# version4.net
KiCad netlist of a schematic drawn in EAGLE
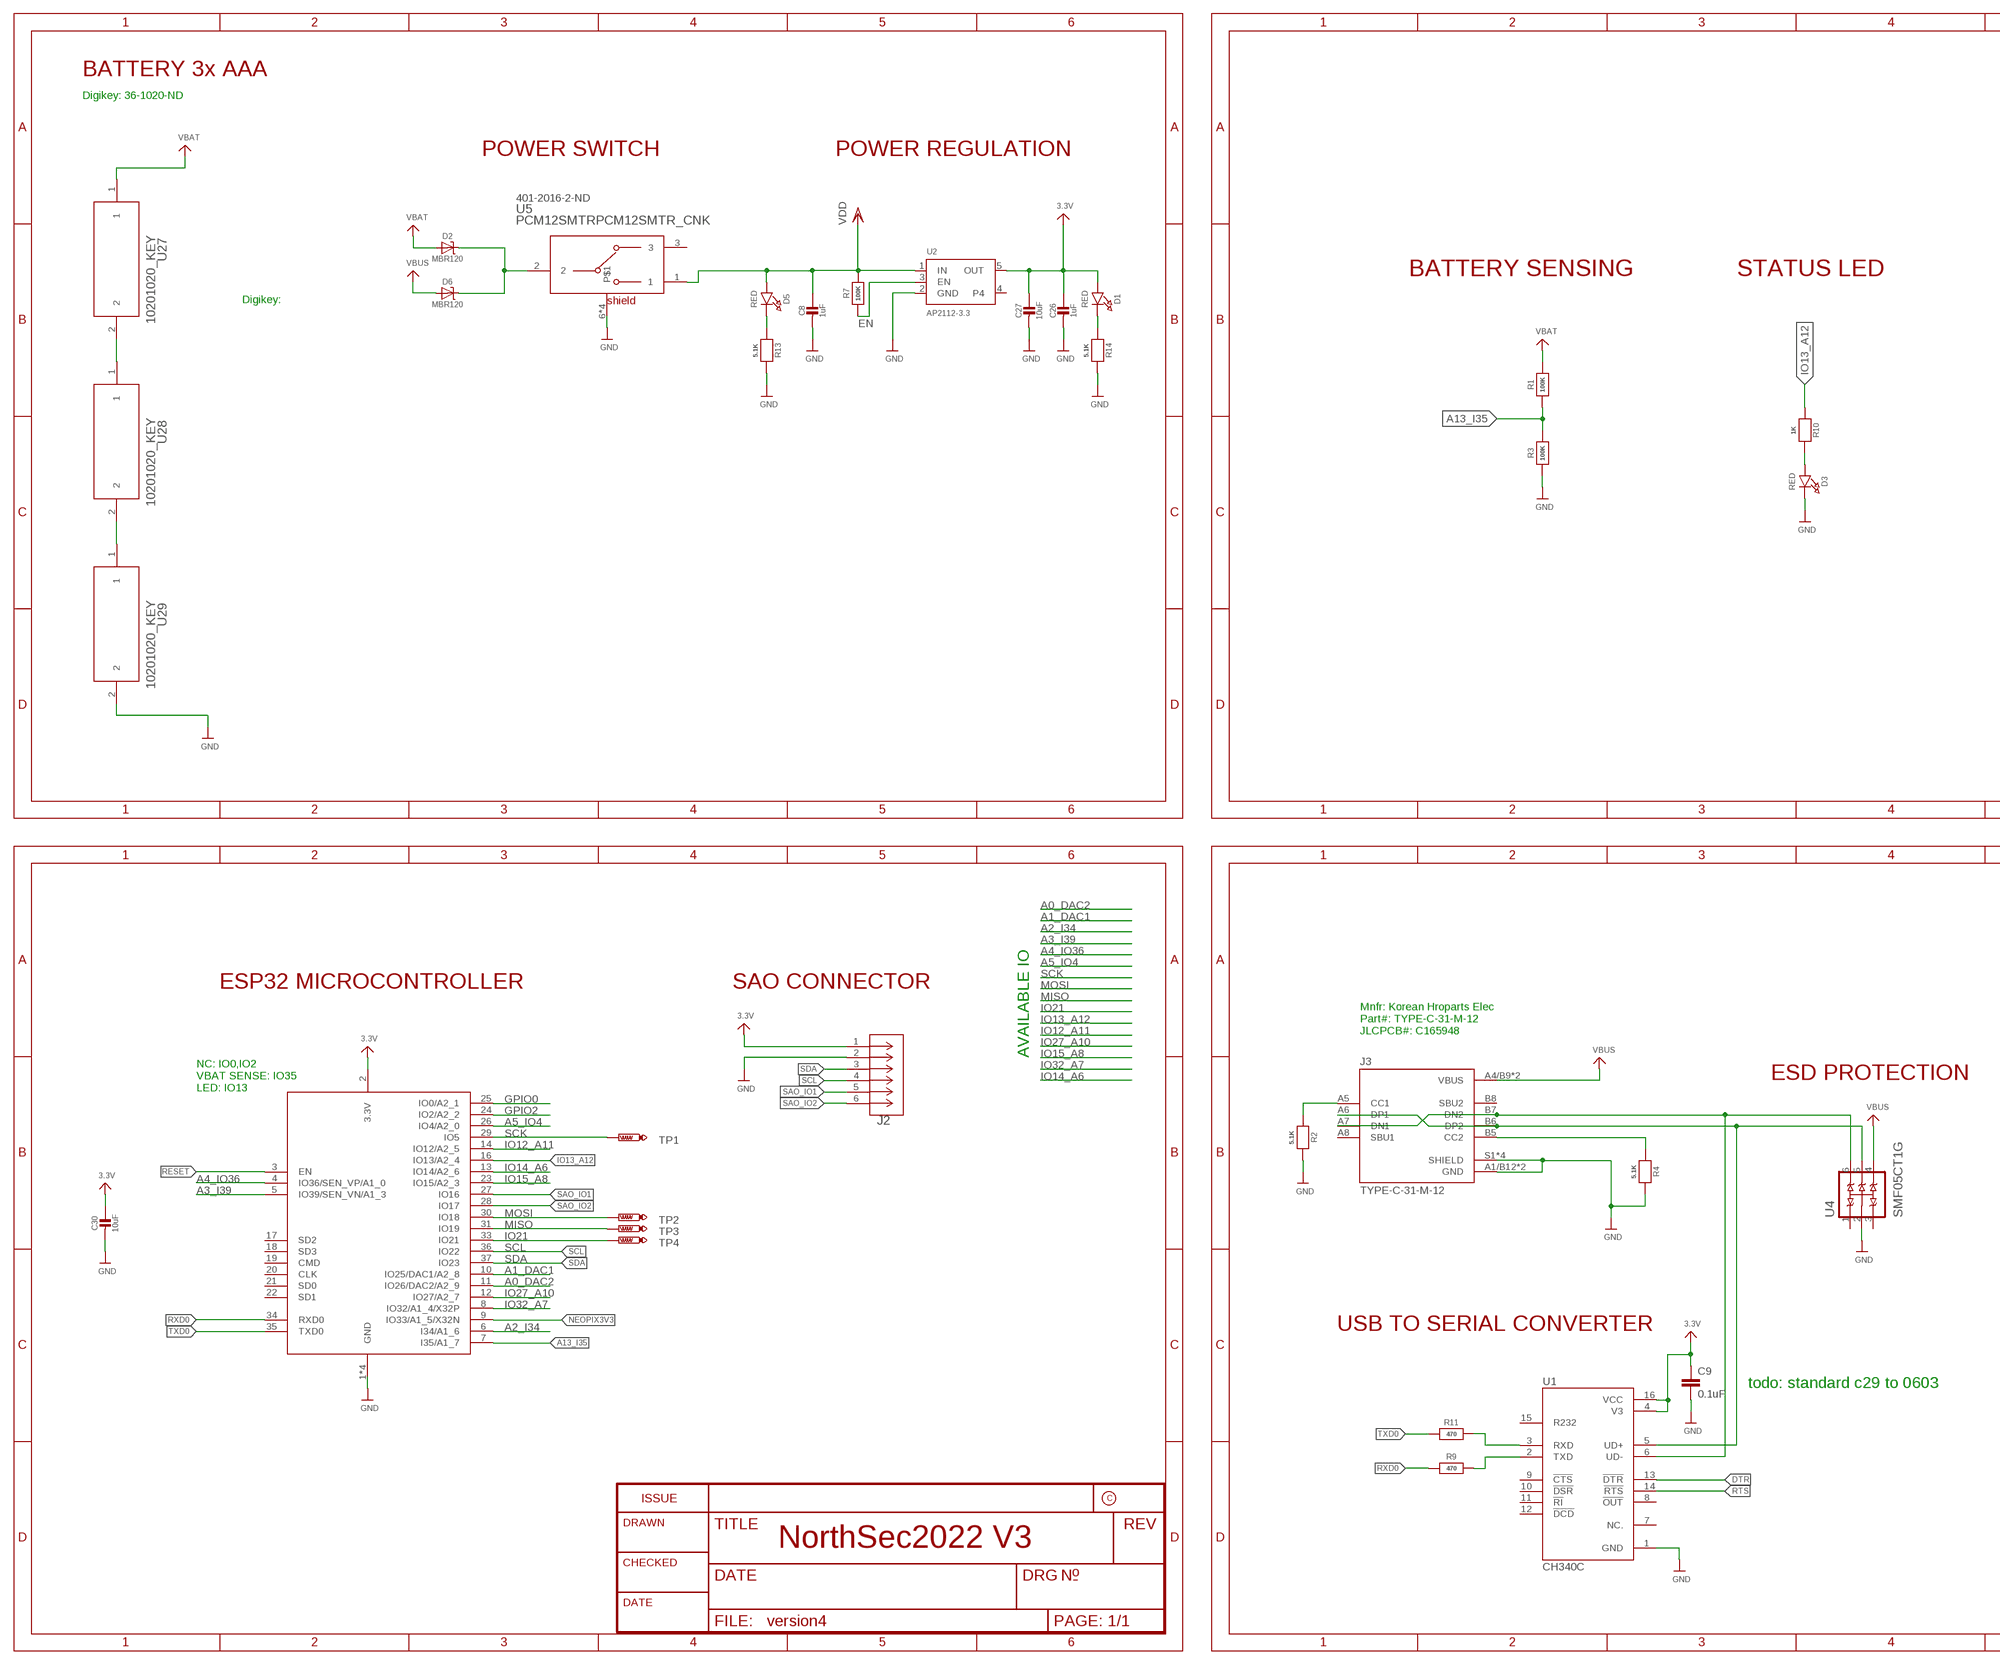
[diagram p0: schematic, sheet 1, part 1 of 2]
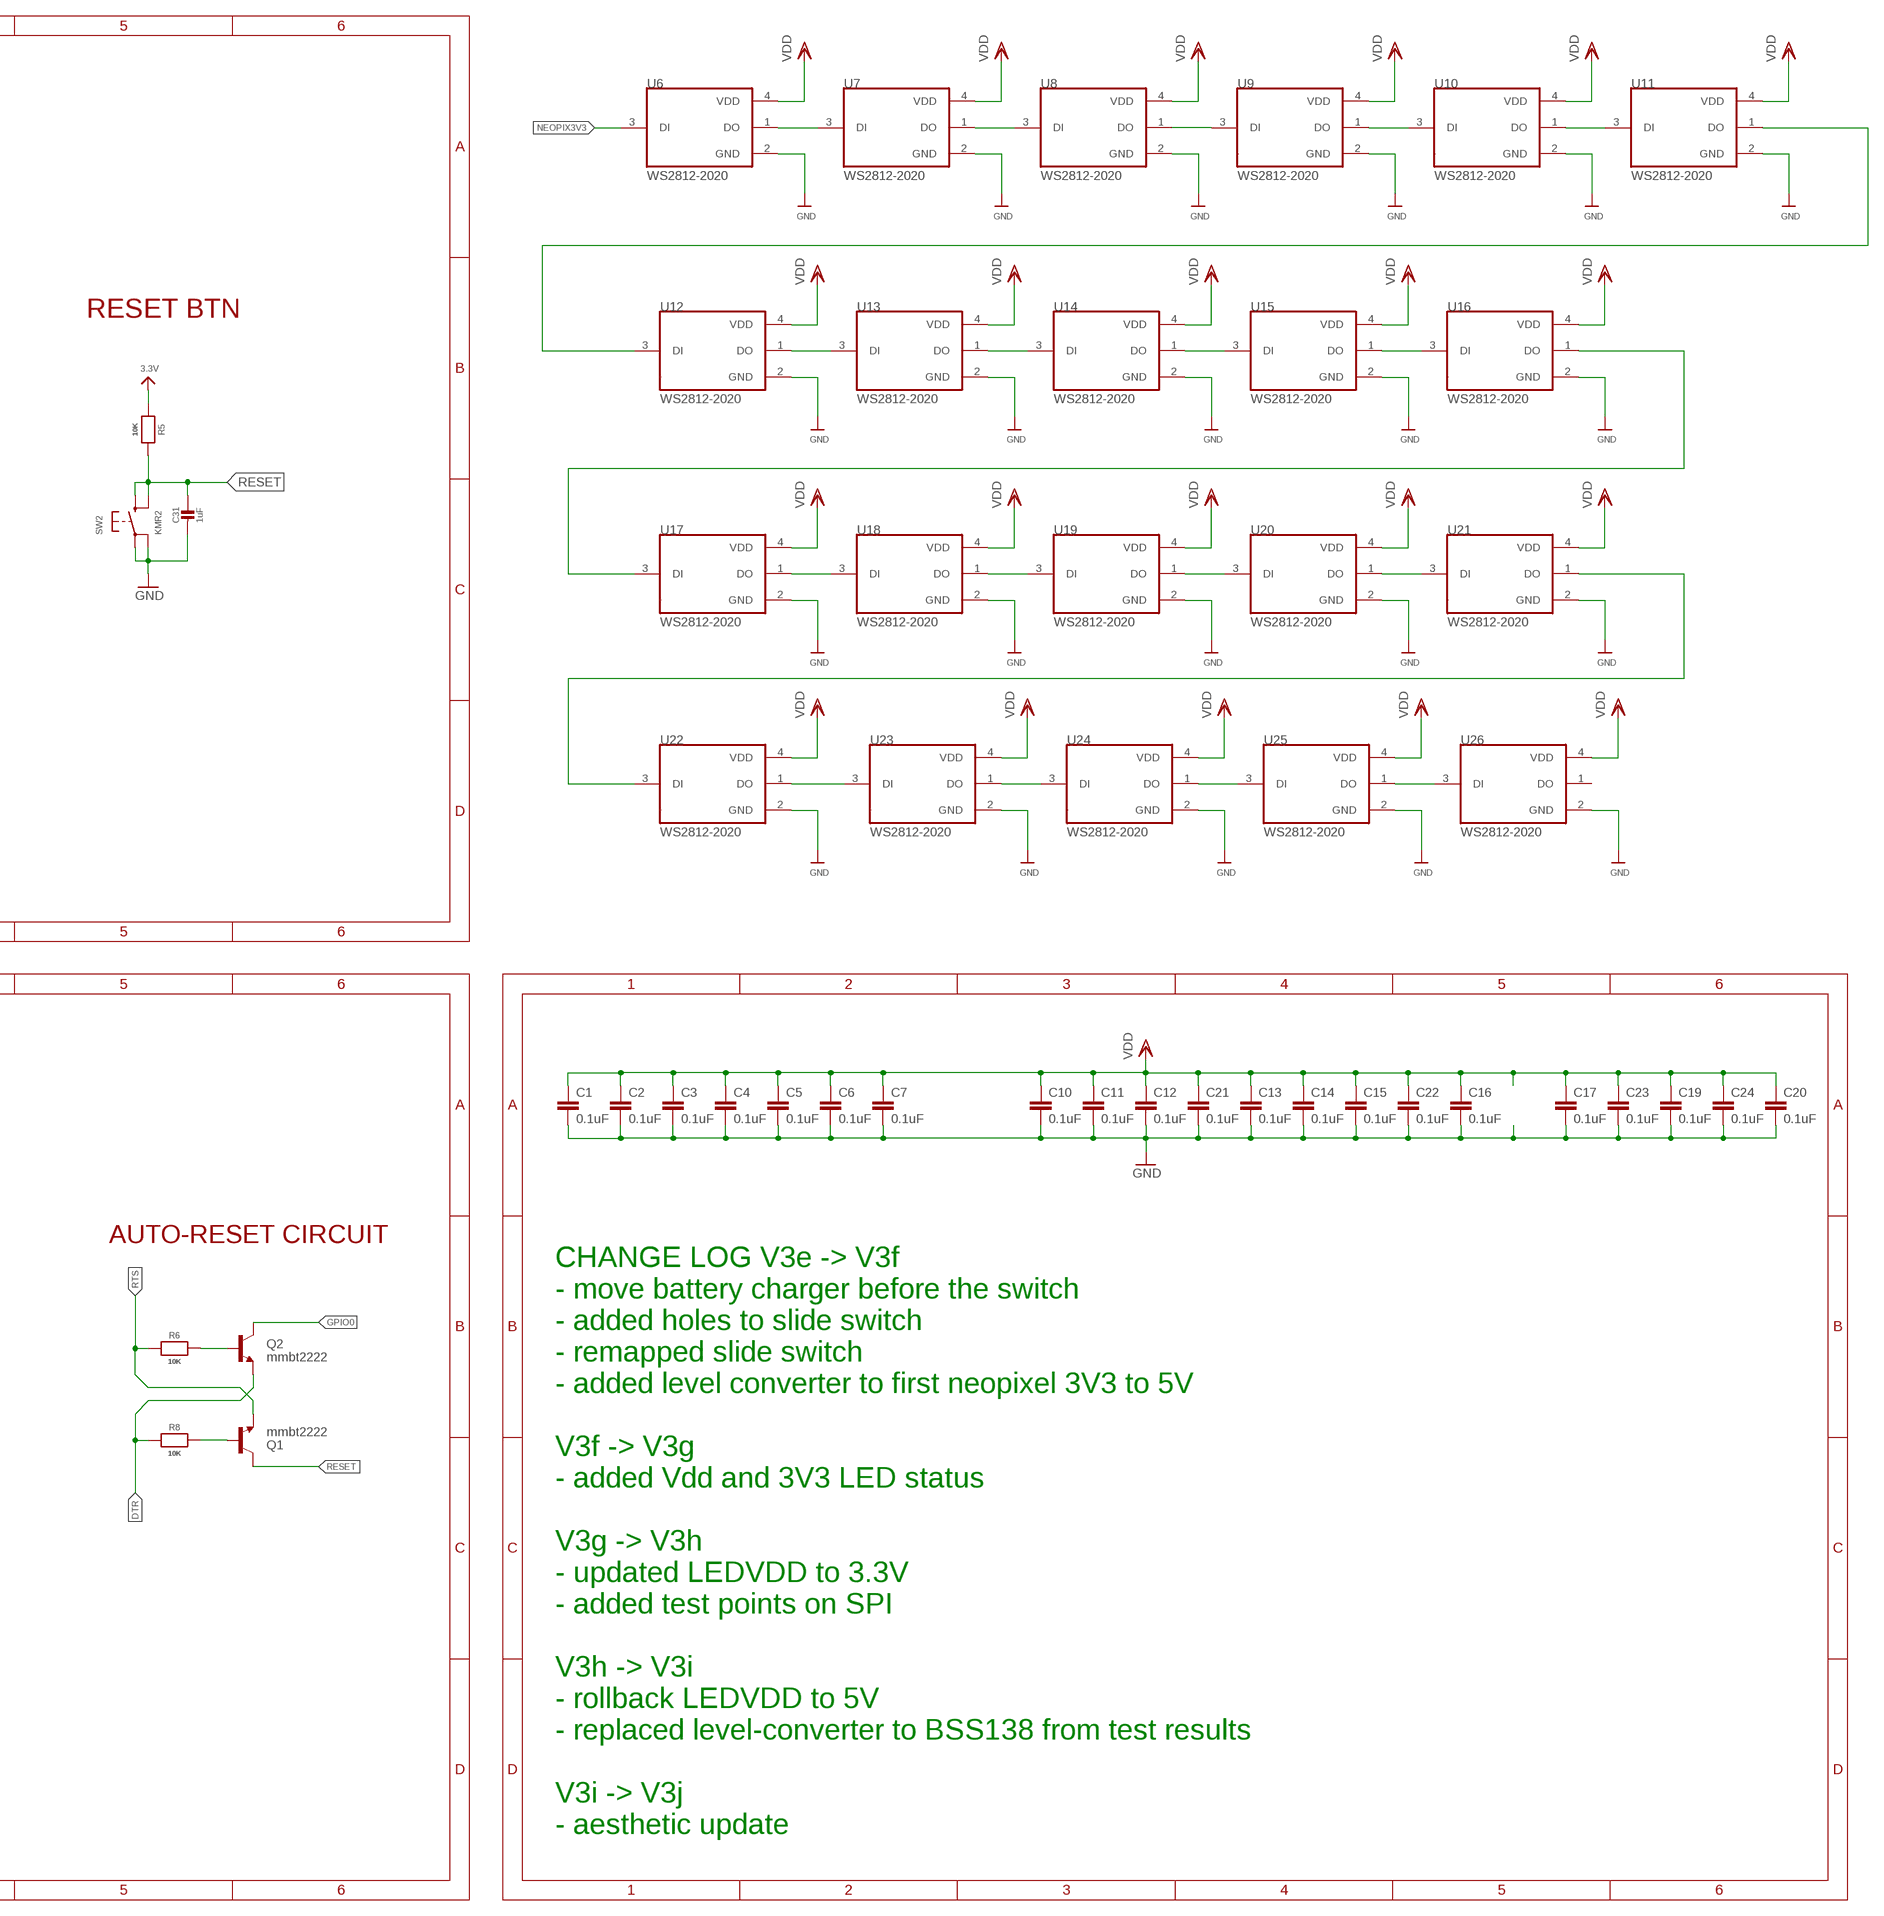
[diagram p1: schematic, sheet 1, part 2 of 2]

(export (version "E")
  (design (tool "Eeschema 10.0.6"))
  (components
    (comp (ref "C1")
      (value "0.1uF")
      (footprint "eagle-import:C0603")
      (libsource (lib "eagle-import") (part "C-EUC0603"))
    )
    (comp (ref "C2")
      (value "0.1uF")
      (footprint "eagle-import:C0603")
      (libsource (lib "eagle-import") (part "C-EUC0603"))
    )
    (comp (ref "C3")
      (value "0.1uF")
      (footprint "eagle-import:C0603")
      (libsource (lib "eagle-import") (part "C-EUC0603"))
    )
    (comp (ref "C4")
      (value "0.1uF")
      (footprint "eagle-import:C0603")
      (libsource (lib "eagle-import") (part "C-EUC0603"))
    )
    (comp (ref "C5")
      (value "0.1uF")
      (footprint "eagle-import:C0603")
      (libsource (lib "eagle-import") (part "C-EUC0603"))
    )
    (comp (ref "C6")
      (value "0.1uF")
      (footprint "eagle-import:C0603")
      (libsource (lib "eagle-import") (part "C-EUC0603"))
    )
    (comp (ref "C7")
      (value "0.1uF")
      (footprint "eagle-import:C0603")
      (libsource (lib "eagle-import") (part "C-EUC0603"))
    )
    (comp (ref "C8")
      (value "1uF")
      (footprint "eagle-import:0603-NO")
      (libsource (lib "eagle-import") (part "CAP_CERAMIC0603_NO"))
    )
    (comp (ref "C9")
      (value "0.1uF")
      (footprint "eagle-import:C0603")
      (libsource (lib "eagle-import") (part "C-EUC0603"))
    )
    (comp (ref "C10")
      (value "0.1uF")
      (footprint "eagle-import:C0603")
      (libsource (lib "eagle-import") (part "C-EUC0603"))
    )
    (comp (ref "C11")
      (value "0.1uF")
      (footprint "eagle-import:C0603")
      (libsource (lib "eagle-import") (part "C-EUC0603"))
    )
    (comp (ref "C12")
      (value "0.1uF")
      (footprint "eagle-import:C0603")
      (libsource (lib "eagle-import") (part "C-EUC0603"))
    )
    (comp (ref "C13")
      (value "0.1uF")
      (footprint "eagle-import:C0603")
      (libsource (lib "eagle-import") (part "C-EUC0603"))
    )
    (comp (ref "C14")
      (value "0.1uF")
      (footprint "eagle-import:C0603")
      (libsource (lib "eagle-import") (part "C-EUC0603"))
    )
    (comp (ref "C15")
      (value "0.1uF")
      (footprint "eagle-import:C0603")
      (libsource (lib "eagle-import") (part "C-EUC0603"))
    )
    (comp (ref "C16")
      (value "0.1uF")
      (footprint "eagle-import:C0603")
      (libsource (lib "eagle-import") (part "C-EUC0603"))
    )
    (comp (ref "C17")
      (value "0.1uF")
      (footprint "eagle-import:C0603")
      (libsource (lib "eagle-import") (part "C-EUC0603"))
    )
    (comp (ref "C19")
      (value "0.1uF")
      (footprint "eagle-import:C0603")
      (libsource (lib "eagle-import") (part "C-EUC0603"))
    )
    (comp (ref "C20")
      (value "0.1uF")
      (footprint "eagle-import:C0603")
      (libsource (lib "eagle-import") (part "C-EUC0603"))
    )
    (comp (ref "C21")
      (value "0.1uF")
      (footprint "eagle-import:C0603")
      (libsource (lib "eagle-import") (part "C-EUC0603"))
    )
    (comp (ref "C22")
      (value "0.1uF")
      (footprint "eagle-import:C0603")
      (libsource (lib "eagle-import") (part "C-EUC0603"))
    )
    (comp (ref "C23")
      (value "0.1uF")
      (footprint "eagle-import:C0603")
      (libsource (lib "eagle-import") (part "C-EUC0603"))
    )
    (comp (ref "C24")
      (value "0.1uF")
      (footprint "eagle-import:C0603")
      (libsource (lib "eagle-import") (part "C-EUC0603"))
    )
    (comp (ref "C26")
      (value "1uF")
      (footprint "eagle-import:0603-NO")
      (libsource (lib "eagle-import") (part "CAP_CERAMIC0603_NO"))
    )
    (comp (ref "C27")
      (value "10uF")
      (footprint "eagle-import:0805-NO")
      (libsource (lib "eagle-import") (part "CAP_CERAMIC0805-NOOUTLINE"))
    )
    (comp (ref "C30")
      (value "10uF")
      (footprint "eagle-import:0805-NO")
      (libsource (lib "eagle-import") (part "CAP_CERAMIC0805-NOOUTLINE"))
    )
    (comp (ref "C31")
      (value "1uF")
      (footprint "eagle-import:0603-NO")
      (libsource (lib "eagle-import") (part "CAP_CERAMIC0603_NO"))
    )
    (comp (ref "D1")
      (value "RED")
      (footprint "eagle-import:CHIPLED_0805_NOOUTLINE")
      (libsource (lib "eagle-import") (part "LED0805_NOOUTLINE"))
    )
    (comp (ref "D2")
      (value "MBR120")
      (footprint "eagle-import:SOD-123")
      (libsource (lib "eagle-import") (part "DIODE-SCHOTTKYSOD-123"))
    )
    (comp (ref "D3")
      (value "RED")
      (footprint "eagle-import:CHIPLED_0805_NOOUTLINE")
      (libsource (lib "eagle-import") (part "LED0805_NOOUTLINE"))
    )
    (comp (ref "D5")
      (value "RED")
      (footprint "eagle-import:CHIPLED_0805_NOOUTLINE")
      (libsource (lib "eagle-import") (part "LED0805_NOOUTLINE"))
    )
    (comp (ref "D6")
      (value "MBR120")
      (footprint "eagle-import:SOD-123")
      (libsource (lib "eagle-import") (part "DIODE-SCHOTTKYSOD-123"))
    )
    (comp (ref "J2")
      (value "SSW-103-22-F-D-VS-K-TRCON3_SSW-D-DUMZ_HDR_SAI")
      (footprint "eagle-import:CON3_SSW-D-DUMZ_HDR_SAI")
      (fields
        (field (name "MANUFACTURER_PART_NUMBER") "SSW-103-22-F-D-VS-K-TR")
        (field (name "COPYRIGHT") "Copyright (C) 2022 Ultra Librarian. All rights reserved.")
      )
      (libsource (lib "eagle-import") (part "SSW-103-22-F-D-VS-K-TRCON3_SSW-D-DUMZ_HDR_SAI"))
    )
    (comp (ref "J3")
      (value "TYPE-C-31-M-12")
      (footprint "eagle-import:HRO_TYPE-C-31-M-12")
      (fields (field (name "MANUFACTURER") "HRO Electronics Co., Ltd."))
      (libsource (lib "eagle-import") (part "TYPE-C-31-M-12"))
    )
    (comp (ref "Q1")
      (value "mmbt2222")
      (footprint "eagle-import:SOT23-3")
      (libsource (lib "eagle-import") (part "TRANSISTOR_NPNSOT23-3"))
    )
    (comp (ref "Q2")
      (value "mmbt2222")
      (footprint "eagle-import:SOT23-3")
      (libsource (lib "eagle-import") (part "TRANSISTOR_NPNSOT23-3"))
    )
    (comp (ref "R1")
      (value "100K")
      (footprint "eagle-import:0603-NO")
      (libsource (lib "eagle-import") (part "RESISTOR_0603_NOOUT"))
    )
    (comp (ref "R2")
      (value "5.1K")
      (footprint "eagle-import:0603-NO")
      (libsource (lib "eagle-import") (part "RESISTOR_0603_NOOUT"))
    )
    (comp (ref "R3")
      (value "100K")
      (footprint "eagle-import:0603-NO")
      (libsource (lib "eagle-import") (part "RESISTOR_0603_NOOUT"))
    )
    (comp (ref "R4")
      (value "5.1K")
      (footprint "eagle-import:0603-NO")
      (libsource (lib "eagle-import") (part "RESISTOR_0603_NOOUT"))
    )
    (comp (ref "R5")
      (value "10K")
      (footprint "eagle-import:0603-NO")
      (libsource (lib "eagle-import") (part "RESISTOR_0603_NOOUT"))
    )
    (comp (ref "R6")
      (value "10K")
      (footprint "eagle-import:0603-NO")
      (libsource (lib "eagle-import") (part "RESISTOR_0603_NOOUT"))
    )
    (comp (ref "R7")
      (value "100K")
      (footprint "eagle-import:0603-NO")
      (libsource (lib "eagle-import") (part "RESISTOR_0603_NOOUT"))
    )
    (comp (ref "R8")
      (value "10K")
      (footprint "eagle-import:0603-NO")
      (libsource (lib "eagle-import") (part "RESISTOR_0603_NOOUT"))
    )
    (comp (ref "R9")
      (value "470")
      (footprint "eagle-import:0603-NO")
      (libsource (lib "eagle-import") (part "RESISTOR_0603_NOOUT"))
    )
    (comp (ref "R10")
      (value "1K")
      (footprint "eagle-import:0603-NO")
      (libsource (lib "eagle-import") (part "RESISTOR_0603_NOOUT"))
    )
    (comp (ref "R11")
      (value "470")
      (footprint "eagle-import:0603-NO")
      (libsource (lib "eagle-import") (part "RESISTOR_0603_NOOUT"))
    )
    (comp (ref "R13")
      (value "5.1K")
      (footprint "eagle-import:0603-NO")
      (libsource (lib "eagle-import") (part "RESISTOR_0603_NOOUT"))
    )
    (comp (ref "R14")
      (value "5.1K")
      (footprint "eagle-import:0603-NO")
      (libsource (lib "eagle-import") (part "RESISTOR_0603_NOOUT"))
    )
    (comp (ref "SW2")
      (value "KMR2")
      (footprint "eagle-import:BTN_KMR2_4.6X2.8")
      (libsource (lib "eagle-import") (part "SWITCH_TACT_SMT4.6X2.8"))
    )
    (comp (ref "TP1")
      (value "PTR1B1,27")
      (footprint "eagle-import:B1,27")
      (libsource (lib "eagle-import") (part "PTR1B1,27"))
    )
    (comp (ref "TP2")
      (value "PTR1B1,27")
      (footprint "eagle-import:B1,27")
      (libsource (lib "eagle-import") (part "PTR1B1,27"))
    )
    (comp (ref "TP3")
      (value "PTR1B1,27")
      (footprint "eagle-import:B1,27")
      (libsource (lib "eagle-import") (part "PTR1B1,27"))
    )
    (comp (ref "TP4")
      (value "PTR1B1,27")
      (footprint "eagle-import:B1,27")
      (libsource (lib "eagle-import") (part "PTR1B1,27"))
    )
    (comp (ref "U1")
      (value "CH340C")
      (footprint "eagle-import:SOIC127P600X180-16N")
      (fields (field (name "MF") "WCH"))
      (libsource (lib "eagle-import") (part "CH340C"))
    )
    (comp (ref "U2")
      (value "AP2112-3.3")
      (footprint "eagle-import:SOT23-5")
      (libsource (lib "eagle-import") (part "VREG_SOT23-5"))
    )
    (comp (ref "U4")
      (value "SMF05CT1G")
      (footprint "eagle-import:SOT65P210X110-6N")
      (fields (field (name "MF") "ON Semiconductor"))
      (libsource (lib "eagle-import") (part "SMF05CT1G"))
    )
    (comp (ref "U5")
      (value "PCM12SMTRPCM12SMTR_CNK")
      (footprint "eagle-import:PCM12SMTR_CNK")
      (fields
        (field (name "MANUFACTURER_PART_NUMBER") "PCM12SMTR")
        (field (name "COPYRIGHT") "Copyright (C) 2022 Ultra Librarian. All rights reserved.")
      )
      (libsource (lib "eagle-import") (part "PCM12SMTRPCM12SMTR_CNK"))
    )
    (comp (ref "U6")
      (value "WS2812-2020")
      (footprint "eagle-import:LED_WS2812-2020")
      (fields (field (name "MF") "Worldsemi"))
      (libsource (lib "eagle-import") (part "WS2812-2020"))
    )
    (comp (ref "U7")
      (value "WS2812-2020")
      (footprint "eagle-import:LED_WS2812-2020")
      (fields (field (name "MF") "Worldsemi"))
      (libsource (lib "eagle-import") (part "WS2812-2020"))
    )
    (comp (ref "U8")
      (value "WS2812-2020")
      (footprint "eagle-import:LED_WS2812-2020")
      (fields (field (name "MF") "Worldsemi"))
      (libsource (lib "eagle-import") (part "WS2812-2020"))
    )
    (comp (ref "U9")
      (value "WS2812-2020")
      (footprint "eagle-import:LED_WS2812-2020")
      (fields (field (name "MF") "Worldsemi"))
      (libsource (lib "eagle-import") (part "WS2812-2020"))
    )
    (comp (ref "U10")
      (value "WS2812-2020")
      (footprint "eagle-import:LED_WS2812-2020")
      (fields (field (name "MF") "Worldsemi"))
      (libsource (lib "eagle-import") (part "WS2812-2020"))
    )
    (comp (ref "U11")
      (value "WS2812-2020")
      (footprint "eagle-import:LED_WS2812-2020")
      (fields (field (name "MF") "Worldsemi"))
      (libsource (lib "eagle-import") (part "WS2812-2020"))
    )
    (comp (ref "U12")
      (value "WS2812-2020")
      (footprint "eagle-import:LED_WS2812-2020")
      (fields (field (name "MF") "Worldsemi"))
      (libsource (lib "eagle-import") (part "WS2812-2020"))
    )
    (comp (ref "U13")
      (value "WS2812-2020")
      (footprint "eagle-import:LED_WS2812-2020")
      (fields (field (name "MF") "Worldsemi"))
      (libsource (lib "eagle-import") (part "WS2812-2020"))
    )
    (comp (ref "U14")
      (value "WS2812-2020")
      (footprint "eagle-import:LED_WS2812-2020")
      (fields (field (name "MF") "Worldsemi"))
      (libsource (lib "eagle-import") (part "WS2812-2020"))
    )
    (comp (ref "U15")
      (value "WS2812-2020")
      (footprint "eagle-import:LED_WS2812-2020")
      (fields (field (name "MF") "Worldsemi"))
      (libsource (lib "eagle-import") (part "WS2812-2020"))
    )
    (comp (ref "U16")
      (value "WS2812-2020")
      (footprint "eagle-import:LED_WS2812-2020")
      (fields (field (name "MF") "Worldsemi"))
      (libsource (lib "eagle-import") (part "WS2812-2020"))
    )
    (comp (ref "U17")
      (value "WS2812-2020")
      (footprint "eagle-import:LED_WS2812-2020")
      (fields (field (name "MF") "Worldsemi"))
      (libsource (lib "eagle-import") (part "WS2812-2020"))
    )
    (comp (ref "U18")
      (value "WS2812-2020")
      (footprint "eagle-import:LED_WS2812-2020")
      (fields (field (name "MF") "Worldsemi"))
      (libsource (lib "eagle-import") (part "WS2812-2020"))
    )
    (comp (ref "U19")
      (value "WS2812-2020")
      (footprint "eagle-import:LED_WS2812-2020")
      (fields (field (name "MF") "Worldsemi"))
      (libsource (lib "eagle-import") (part "WS2812-2020"))
    )
    (comp (ref "U20")
      (value "WS2812-2020")
      (footprint "eagle-import:LED_WS2812-2020")
      (fields (field (name "MF") "Worldsemi"))
      (libsource (lib "eagle-import") (part "WS2812-2020"))
    )
    (comp (ref "U21")
      (value "WS2812-2020")
      (footprint "eagle-import:LED_WS2812-2020")
      (fields (field (name "MF") "Worldsemi"))
      (libsource (lib "eagle-import") (part "WS2812-2020"))
    )
    (comp (ref "U22")
      (value "WS2812-2020")
      (footprint "eagle-import:LED_WS2812-2020")
      (fields (field (name "MF") "Worldsemi"))
      (libsource (lib "eagle-import") (part "WS2812-2020"))
    )
    (comp (ref "U23")
      (value "WS2812-2020")
      (footprint "eagle-import:LED_WS2812-2020")
      (fields (field (name "MF") "Worldsemi"))
      (libsource (lib "eagle-import") (part "WS2812-2020"))
    )
    (comp (ref "U24")
      (value "WS2812-2020")
      (footprint "eagle-import:LED_WS2812-2020")
      (fields (field (name "MF") "Worldsemi"))
      (libsource (lib "eagle-import") (part "WS2812-2020"))
    )
    (comp (ref "U25")
      (value "WS2812-2020")
      (footprint "eagle-import:LED_WS2812-2020")
      (fields (field (name "MF") "Worldsemi"))
      (libsource (lib "eagle-import") (part "WS2812-2020"))
    )
    (comp (ref "U26")
      (value "WS2812-2020")
      (footprint "eagle-import:LED_WS2812-2020")
      (fields (field (name "MF") "Worldsemi"))
      (libsource (lib "eagle-import") (part "WS2812-2020"))
    )
    (comp (ref "U27")
      (value "10201020_KEY")
      (footprint "eagle-import:1020_KEY")
      (fields
        (field (name "MANUFACTURER_PART_NUMBER") "1020")
        (field (name "COPYRIGHT") "Copyright (C) 2022 Ultra Librarian. All rights reserved.")
      )
      (libsource (lib "eagle-import") (part "10201020_KEY"))
    )
    (comp (ref "U28")
      (value "10201020_KEY")
      (footprint "eagle-import:1020_KEY")
      (fields
        (field (name "MANUFACTURER_PART_NUMBER") "1020")
        (field (name "COPYRIGHT") "Copyright (C) 2022 Ultra Librarian. All rights reserved.")
      )
      (libsource (lib "eagle-import") (part "10201020_KEY"))
    )
    (comp (ref "U29")
      (value "10201020_KEY")
      (footprint "eagle-import:1020_KEY")
      (fields
        (field (name "MANUFACTURER_PART_NUMBER") "1020")
        (field (name "COPYRIGHT") "Copyright (C) 2022 Ultra Librarian. All rights reserved.")
      )
      (libsource (lib "eagle-import") (part "10201020_KEY"))
    )
    (comp (ref "X2")
      (value "ESP32_WROOM32_SKINNY")
      (footprint "eagle-import:WROOM32_SKINNY")
      (libsource (lib "eagle-import") (part "ESP32_WROOM32_SKINNY"))
    )
  )
  (nets
    (net (code "1") (name "/A0_DAC2") (class "Default")
      (node (ref "X2") (pin "11") (pinfunction "IO26/DAC2/A2_9_11") (pintype "bidirectional"))
    )
    (net (code "2") (name "/A1_DAC1") (class "Default")
      (node (ref "X2") (pin "10") (pinfunction "IO25/DAC1/A2_8_10") (pintype "bidirectional"))
    )
    (net (code "3") (name "/A2_I34") (class "Default")
      (node (ref "X2") (pin "6") (pinfunction "I34/A1_6_6") (pintype "bidirectional"))
    )
    (net (code "4") (name "/A3_I39") (class "Default")
      (node (ref "X2") (pin "5") (pinfunction "IO39/SEN_VN/A1_3_5") (pintype "passive"))
    )
    (net (code "5") (name "/A4_IO36") (class "Default")
      (node (ref "X2") (pin "4") (pinfunction "IO36/SEN_VP/A1_0_4") (pintype "passive"))
    )
    (net (code "6") (name "/A5_IO4") (class "Default")
      (node (ref "X2") (pin "26") (pinfunction "IO4/A2_0_26") (pintype "bidirectional"))
    )
    (net (code "7") (name "/EN") (class "Default")
      (node (ref "R7") (pin "1") (pinfunction "1_1") (pintype "passive"))
      (node (ref "U2") (pin "3") (pinfunction "EN_3") (pintype "input"))
    )
    (net (code "8") (name "/GPIO2") (class "Default")
      (node (ref "X2") (pin "24") (pinfunction "IO2/A2_2_24") (pintype "bidirectional"))
    )
    (net (code "9") (name "/IO12_A11") (class "Default")
      (node (ref "X2") (pin "14") (pinfunction "IO12/A2_5_14") (pintype "bidirectional"))
    )
    (net (code "10") (name "/IO14_A6") (class "Default")
      (node (ref "X2") (pin "13") (pinfunction "IO14/A2_6_13") (pintype "bidirectional"))
    )
    (net (code "11") (name "/IO15_A8") (class "Default")
      (node (ref "X2") (pin "23") (pinfunction "IO15/A2_3_23") (pintype "bidirectional"))
    )
    (net (code "12") (name "/IO21") (class "Default")
      (node (ref "TP4") (pin "TP") (pinfunction "TP_TP") (pintype "input"))
      (node (ref "X2") (pin "33") (pinfunction "IO21_33") (pintype "bidirectional"))
    )
    (net (code "13") (name "/IO27_A10") (class "Default")
      (node (ref "X2") (pin "12") (pinfunction "IO27/A2_7_12") (pintype "bidirectional"))
    )
    (net (code "14") (name "/IO32_A7") (class "Default")
      (node (ref "X2") (pin "8") (pinfunction "IO32/A1_4/X32P_8") (pintype "bidirectional"))
    )
    (net (code "15") (name "/MISO") (class "Default")
      (node (ref "TP3") (pin "TP") (pinfunction "TP_TP") (pintype "input"))
      (node (ref "X2") (pin "31") (pinfunction "IO19_31") (pintype "bidirectional"))
    )
    (net (code "16") (name "/MOSI") (class "Default")
      (node (ref "TP2") (pin "TP") (pinfunction "TP_TP") (pintype "input"))
      (node (ref "X2") (pin "30") (pinfunction "IO18_30") (pintype "bidirectional"))
    )
    (net (code "17") (name "/SCK") (class "Default")
      (node (ref "TP1") (pin "TP") (pinfunction "TP_TP") (pintype "input"))
      (node (ref "X2") (pin "29") (pinfunction "IO5_29") (pintype "bidirectional"))
    )
    (net (code "18") (name "3.3V") (class "Default")
      (node (ref "C26") (pin "1") (pinfunction "1_1") (pintype "passive"))
      (node (ref "C27") (pin "1") (pinfunction "1_1") (pintype "passive"))
      (node (ref "C30") (pin "1") (pinfunction "1_1") (pintype "passive"))
      (node (ref "C9") (pin "1") (pinfunction "1_1") (pintype "passive"))
      (node (ref "D1") (pin "A") (pinfunction "A_A") (pintype "passive"))
      (node (ref "J2") (pin "1") (pinfunction "1_1") (pintype "passive"))
      (node (ref "R5") (pin "1") (pinfunction "1_1") (pintype "passive"))
      (node (ref "U1") (pin "16") (pinfunction "VCC_16") (pintype "power_in"))
      (node (ref "U1") (pin "4") (pinfunction "V3_4") (pintype "power_in"))
      (node (ref "U2") (pin "5") (pinfunction "OUT_5") (pintype "power_in"))
      (node (ref "X2") (pin "2") (pinfunction "3.3V_2") (pintype "passive"))
    )
    (net (code "19") (name "A13_I35") (class "Default")
      (node (ref "R1") (pin "1") (pinfunction "1_1") (pintype "passive"))
      (node (ref "R3") (pin "2") (pinfunction "2_2") (pintype "passive"))
      (node (ref "X2") (pin "7") (pinfunction "I35/A1_7_7") (pintype "bidirectional"))
    )
    (net (code "20") (name "DTR") (class "Default")
      (node (ref "Q2") (pin "2") (pinfunction "E_2") (pintype "passive"))
      (node (ref "R8") (pin "1") (pinfunction "1_1") (pintype "passive"))
      (node (ref "U1") (pin "13") (pinfunction "~{DTR}_13") (pintype "output"))
    )
    (net (code "21") (name "GND") (class "Default")
      (node (ref "C1") (pin "2") (pinfunction "2_2") (pintype "passive"))
      (node (ref "C10") (pin "2") (pinfunction "2_2") (pintype "passive"))
      (node (ref "C11") (pin "2") (pinfunction "2_2") (pintype "passive"))
      (node (ref "C12") (pin "2") (pinfunction "2_2") (pintype "passive"))
      (node (ref "C13") (pin "2") (pinfunction "2_2") (pintype "passive"))
      (node (ref "C14") (pin "2") (pinfunction "2_2") (pintype "passive"))
      (node (ref "C15") (pin "2") (pinfunction "2_2") (pintype "passive"))
      (node (ref "C16") (pin "2") (pinfunction "2_2") (pintype "passive"))
      (node (ref "C17") (pin "2") (pinfunction "2_2") (pintype "passive"))
      (node (ref "C19") (pin "2") (pinfunction "2_2") (pintype "passive"))
      (node (ref "C2") (pin "2") (pinfunction "2_2") (pintype "passive"))
      (node (ref "C20") (pin "2") (pinfunction "2_2") (pintype "passive"))
      (node (ref "C21") (pin "2") (pinfunction "2_2") (pintype "passive"))
      (node (ref "C22") (pin "2") (pinfunction "2_2") (pintype "passive"))
      (node (ref "C23") (pin "2") (pinfunction "2_2") (pintype "passive"))
      (node (ref "C24") (pin "2") (pinfunction "2_2") (pintype "passive"))
      (node (ref "C26") (pin "2") (pinfunction "2_2") (pintype "passive"))
      (node (ref "C27") (pin "2") (pinfunction "2_2") (pintype "passive"))
      (node (ref "C3") (pin "2") (pinfunction "2_2") (pintype "passive"))
      (node (ref "C30") (pin "2") (pinfunction "2_2") (pintype "passive"))
      (node (ref "C31") (pin "2") (pinfunction "2_2") (pintype "passive"))
      (node (ref "C4") (pin "2") (pinfunction "2_2") (pintype "passive"))
      (node (ref "C5") (pin "2") (pinfunction "2_2") (pintype "passive"))
      (node (ref "C6") (pin "2") (pinfunction "2_2") (pintype "passive"))
      (node (ref "C7") (pin "2") (pinfunction "2_2") (pintype "passive"))
      (node (ref "C8") (pin "2") (pinfunction "2_2") (pintype "passive"))
      (node (ref "C9") (pin "2") (pinfunction "2_2") (pintype "passive"))
      (node (ref "D3") (pin "C") (pinfunction "C_C") (pintype "passive"))
      (node (ref "J2") (pin "2") (pinfunction "2_2") (pintype "passive"))
      (node (ref "J3") (pin "A1/B12") (pinfunction "GND_A1/B12") (pintype "power_in"))
      (node (ref "J3") (pin "B1/A12") (pinfunction "GND_B1/A12") (pintype "power_in"))
      (node (ref "J3") (pin "S1") (pinfunction "SHIELD_S1") (pintype "passive"))
      (node (ref "J3") (pin "S2") (pinfunction "SHIELD_S2") (pintype "passive"))
      (node (ref "J3") (pin "S3") (pinfunction "SHIELD_S3") (pintype "passive"))
      (node (ref "J3") (pin "S4") (pinfunction "SHIELD_S4") (pintype "passive"))
      (node (ref "R13") (pin "2") (pinfunction "2_2") (pintype "passive"))
      (node (ref "R14") (pin "2") (pinfunction "2_2") (pintype "passive"))
      (node (ref "R2") (pin "2") (pinfunction "2_2") (pintype "passive"))
      (node (ref "R3") (pin "1") (pinfunction "1_1") (pintype "passive"))
      (node (ref "R4") (pin "2") (pinfunction "2_2") (pintype "passive"))
      (node (ref "SW2") (pin "A") (pinfunction "P_A") (pintype "passive"))
      (node (ref "SW2") (pin "A'") (pinfunction "P1_A'") (pintype "passive"))
      (node (ref "U1") (pin "1") (pinfunction "GND_1") (pintype "power_in"))
      (node (ref "U10") (pin "2") (pinfunction "GND_2") (pintype "power_in"))
      (node (ref "U11") (pin "2") (pinfunction "GND_2") (pintype "power_in"))
      (node (ref "U12") (pin "2") (pinfunction "GND_2") (pintype "power_in"))
      (node (ref "U13") (pin "2") (pinfunction "GND_2") (pintype "power_in"))
      (node (ref "U14") (pin "2") (pinfunction "GND_2") (pintype "power_in"))
      (node (ref "U15") (pin "2") (pinfunction "GND_2") (pintype "power_in"))
      (node (ref "U16") (pin "2") (pinfunction "GND_2") (pintype "power_in"))
      (node (ref "U17") (pin "2") (pinfunction "GND_2") (pintype "power_in"))
      (node (ref "U18") (pin "2") (pinfunction "GND_2") (pintype "power_in"))
      (node (ref "U19") (pin "2") (pinfunction "GND_2") (pintype "power_in"))
      (node (ref "U2") (pin "2") (pinfunction "GND_2") (pintype "power_in"))
      (node (ref "U20") (pin "2") (pinfunction "GND_2") (pintype "power_in"))
      (node (ref "U21") (pin "2") (pinfunction "GND_2") (pintype "power_in"))
      (node (ref "U22") (pin "2") (pinfunction "GND_2") (pintype "power_in"))
      (node (ref "U23") (pin "2") (pinfunction "GND_2") (pintype "power_in"))
      (node (ref "U24") (pin "2") (pinfunction "GND_2") (pintype "power_in"))
      (node (ref "U25") (pin "2") (pinfunction "GND_2") (pintype "power_in"))
      (node (ref "U26") (pin "2") (pinfunction "GND_2") (pintype "power_in"))
      (node (ref "U29") (pin "2") (pinfunction "2_2") (pintype "passive"))
      (node (ref "U4") (pin "2") (pinfunction "A_2") (pintype "passive"))
      (node (ref "U5") (pin "6") (pinfunction "P$1_6") (pintype "bidirectional"))
      (node (ref "U5") (pin "7") (pinfunction "P$1_7") (pintype "bidirectional"))
      (node (ref "U5") (pin "8") (pinfunction "P$1_8") (pintype "bidirectional"))
      (node (ref "U5") (pin "9") (pinfunction "P$1_9") (pintype "bidirectional"))
      (node (ref "U6") (pin "2") (pinfunction "GND_2") (pintype "power_in"))
      (node (ref "U7") (pin "2") (pinfunction "GND_2") (pintype "power_in"))
      (node (ref "U8") (pin "2") (pinfunction "GND_2") (pintype "power_in"))
      (node (ref "U9") (pin "2") (pinfunction "GND_2") (pintype "power_in"))
      (node (ref "X2") (pin "1") (pinfunction "GND_1") (pintype "passive"))
      (node (ref "X2") (pin "15") (pinfunction "GND_15") (pintype "passive"))
      (node (ref "X2") (pin "38") (pinfunction "GND_38") (pintype "passive"))
      (node (ref "X2") (pin "P$1") (pinfunction "GND_P$1") (pintype "passive"))
    )
    (net (code "22") (name "GPIO0") (class "Default")
      (node (ref "Q2") (pin "3") (pinfunction "C_3") (pintype "passive"))
      (node (ref "X2") (pin "25") (pinfunction "IO0/A2_1_25") (pintype "bidirectional"))
    )
    (net (code "23") (name "IO13_A12") (class "Default")
      (node (ref "R10") (pin "1") (pinfunction "1_1") (pintype "passive"))
      (node (ref "X2") (pin "16") (pinfunction "IO13/A2_4_16") (pintype "bidirectional"))
    )
    (net (code "24") (name "NEOPIX3V3") (class "Default")
      (node (ref "U6") (pin "3") (pinfunction "DI_3") (pintype "input"))
      (node (ref "X2") (pin "9") (pinfunction "IO33/A1_5/X32N_9") (pintype "bidirectional"))
    )
    (net (code "25") (name "Net-(D1-PadC)") (class "Default")
      (node (ref "D1") (pin "C") (pinfunction "C_C") (pintype "passive"))
      (node (ref "R14") (pin "1") (pinfunction "1_1") (pintype "passive"))
    )
    (net (code "26") (name "Net-(D2-PadC)") (class "Default")
      (node (ref "D2") (pin "C") (pinfunction "C_C") (pintype "passive"))
      (node (ref "D6") (pin "C") (pinfunction "C_C") (pintype "passive"))
      (node (ref "U5") (pin "2") (pinfunction "2_2") (pintype "passive"))
    )
    (net (code "27") (name "Net-(D3-PadA)") (class "Default")
      (node (ref "D3") (pin "A") (pinfunction "A_A") (pintype "passive"))
      (node (ref "R10") (pin "2") (pinfunction "2_2") (pintype "passive"))
    )
    (net (code "28") (name "Net-(D5-PadC)") (class "Default")
      (node (ref "D5") (pin "C") (pinfunction "C_C") (pintype "passive"))
      (node (ref "R13") (pin "1") (pinfunction "1_1") (pintype "passive"))
    )
    (net (code "29") (name "Net-(J3-CC1)") (class "Default")
      (node (ref "J3") (pin "A5") (pinfunction "CC1_A5") (pintype "bidirectional"))
      (node (ref "R2") (pin "1") (pinfunction "1_1") (pintype "passive"))
    )
    (net (code "30") (name "Net-(J3-CC2)") (class "Default")
      (node (ref "J3") (pin "B5") (pinfunction "CC2_B5") (pintype "bidirectional"))
      (node (ref "R4") (pin "1") (pinfunction "1_1") (pintype "passive"))
    )
    (net (code "31") (name "Net-(J3-DN1)") (class "Default")
      (node (ref "J3") (pin "A7") (pinfunction "DN1_A7") (pintype "bidirectional"))
      (node (ref "J3") (pin "B7") (pinfunction "DN2_B7") (pintype "bidirectional"))
      (node (ref "U1") (pin "6") (pinfunction "UD-_6") (pintype "bidirectional"))
      (node (ref "U4") (pin "6") (pinfunction "C5_6") (pintype "passive"))
    )
    (net (code "32") (name "Net-(J3-DP1)") (class "Default")
      (node (ref "J3") (pin "A6") (pinfunction "DP1_A6") (pintype "bidirectional"))
      (node (ref "J3") (pin "B6") (pinfunction "DP2_B6") (pintype "bidirectional"))
      (node (ref "U1") (pin "5") (pinfunction "UD+_5") (pintype "bidirectional"))
      (node (ref "U4") (pin "5") (pinfunction "C4_5") (pintype "passive"))
    )
    (net (code "33") (name "Net-(Q1-B)") (class "Default")
      (node (ref "Q1") (pin "1") (pinfunction "B_1") (pintype "passive"))
      (node (ref "R8") (pin "2") (pinfunction "2_2") (pintype "passive"))
    )
    (net (code "34") (name "Net-(Q2-B)") (class "Default")
      (node (ref "Q2") (pin "1") (pinfunction "B_1") (pintype "passive"))
      (node (ref "R6") (pin "2") (pinfunction "2_2") (pintype "passive"))
    )
    (net (code "35") (name "Net-(U1-RXD)") (class "Default")
      (node (ref "R11") (pin "2") (pinfunction "2_2") (pintype "passive"))
      (node (ref "U1") (pin "3") (pinfunction "RXD_3") (pintype "input"))
    )
    (net (code "36") (name "Net-(U1-TXD)") (class "Default")
      (node (ref "R9") (pin "2") (pinfunction "2_2") (pintype "passive"))
      (node (ref "U1") (pin "2") (pinfunction "TXD_2") (pintype "output"))
    )
    (net (code "37") (name "Net-(U6-DO)") (class "Default")
      (node (ref "U6") (pin "1") (pinfunction "DO_1") (pintype "output"))
      (node (ref "U7") (pin "3") (pinfunction "DI_3") (pintype "input"))
    )
    (net (code "38") (name "Net-(U7-DO)") (class "Default")
      (node (ref "U7") (pin "1") (pinfunction "DO_1") (pintype "output"))
      (node (ref "U8") (pin "3") (pinfunction "DI_3") (pintype "input"))
    )
    (net (code "39") (name "Net-(U8-DO)") (class "Default")
      (node (ref "U8") (pin "1") (pinfunction "DO_1") (pintype "output"))
      (node (ref "U9") (pin "3") (pinfunction "DI_3") (pintype "input"))
    )
    (net (code "40") (name "Net-(U10-DI)") (class "Default")
      (node (ref "U10") (pin "3") (pinfunction "DI_3") (pintype "input"))
      (node (ref "U9") (pin "1") (pinfunction "DO_1") (pintype "output"))
    )
    (net (code "41") (name "Net-(U10-DO)") (class "Default")
      (node (ref "U10") (pin "1") (pinfunction "DO_1") (pintype "output"))
      (node (ref "U11") (pin "3") (pinfunction "DI_3") (pintype "input"))
    )
    (net (code "42") (name "Net-(U11-DO)") (class "Default")
      (node (ref "U11") (pin "1") (pinfunction "DO_1") (pintype "output"))
      (node (ref "U12") (pin "3") (pinfunction "DI_3") (pintype "input"))
    )
    (net (code "43") (name "Net-(U12-DO)") (class "Default")
      (node (ref "U12") (pin "1") (pinfunction "DO_1") (pintype "output"))
      (node (ref "U13") (pin "3") (pinfunction "DI_3") (pintype "input"))
    )
    (net (code "44") (name "Net-(U13-DO)") (class "Default")
      (node (ref "U13") (pin "1") (pinfunction "DO_1") (pintype "output"))
      (node (ref "U14") (pin "3") (pinfunction "DI_3") (pintype "input"))
    )
    (net (code "45") (name "Net-(U14-DO)") (class "Default")
      (node (ref "U14") (pin "1") (pinfunction "DO_1") (pintype "output"))
      (node (ref "U15") (pin "3") (pinfunction "DI_3") (pintype "input"))
    )
    (net (code "46") (name "Net-(U15-DO)") (class "Default")
      (node (ref "U15") (pin "1") (pinfunction "DO_1") (pintype "output"))
      (node (ref "U16") (pin "3") (pinfunction "DI_3") (pintype "input"))
    )
    (net (code "47") (name "Net-(U16-DO)") (class "Default")
      (node (ref "U16") (pin "1") (pinfunction "DO_1") (pintype "output"))
      (node (ref "U17") (pin "3") (pinfunction "DI_3") (pintype "input"))
    )
    (net (code "48") (name "Net-(U17-DO)") (class "Default")
      (node (ref "U17") (pin "1") (pinfunction "DO_1") (pintype "output"))
      (node (ref "U18") (pin "3") (pinfunction "DI_3") (pintype "input"))
    )
    (net (code "49") (name "Net-(U18-DO)") (class "Default")
      (node (ref "U18") (pin "1") (pinfunction "DO_1") (pintype "output"))
      (node (ref "U19") (pin "3") (pinfunction "DI_3") (pintype "input"))
    )
    (net (code "50") (name "Net-(U19-DO)") (class "Default")
      (node (ref "U19") (pin "1") (pinfunction "DO_1") (pintype "output"))
      (node (ref "U20") (pin "3") (pinfunction "DI_3") (pintype "input"))
    )
    (net (code "51") (name "Net-(U20-DO)") (class "Default")
      (node (ref "U20") (pin "1") (pinfunction "DO_1") (pintype "output"))
      (node (ref "U21") (pin "3") (pinfunction "DI_3") (pintype "input"))
    )
    (net (code "52") (name "Net-(U21-DO)") (class "Default")
      (node (ref "U21") (pin "1") (pinfunction "DO_1") (pintype "output"))
      (node (ref "U22") (pin "3") (pinfunction "DI_3") (pintype "input"))
    )
    (net (code "53") (name "Net-(U22-DO)") (class "Default")
      (node (ref "U22") (pin "1") (pinfunction "DO_1") (pintype "output"))
      (node (ref "U23") (pin "3") (pinfunction "DI_3") (pintype "input"))
    )
    (net (code "54") (name "Net-(U23-DO)") (class "Default")
      (node (ref "U23") (pin "1") (pinfunction "DO_1") (pintype "output"))
      (node (ref "U24") (pin "3") (pinfunction "DI_3") (pintype "input"))
    )
    (net (code "55") (name "Net-(U24-DO)") (class "Default")
      (node (ref "U24") (pin "1") (pinfunction "DO_1") (pintype "output"))
      (node (ref "U25") (pin "3") (pinfunction "DI_3") (pintype "input"))
    )
    (net (code "56") (name "Net-(U25-DO)") (class "Default")
      (node (ref "U25") (pin "1") (pinfunction "DO_1") (pintype "output"))
      (node (ref "U26") (pin "3") (pinfunction "DI_3") (pintype "input"))
    )
    (net (code "57") (name "Net-(U27-Pad2)") (class "Default")
      (node (ref "U27") (pin "2") (pinfunction "2_2") (pintype "passive"))
      (node (ref "U28") (pin "1") (pinfunction "1_1") (pintype "passive"))
    )
    (net (code "58") (name "Net-(U28-Pad2)") (class "Default")
      (node (ref "U28") (pin "2") (pinfunction "2_2") (pintype "passive"))
      (node (ref "U29") (pin "1") (pinfunction "1_1") (pintype "passive"))
    )
    (net (code "59") (name "RESET") (class "Default")
      (node (ref "C31") (pin "1") (pinfunction "1_1") (pintype "passive"))
      (node (ref "Q1") (pin "3") (pinfunction "C_3") (pintype "passive"))
      (node (ref "R5") (pin "2") (pinfunction "2_2") (pintype "passive"))
      (node (ref "SW2") (pin "B") (pinfunction "S_B") (pintype "passive"))
      (node (ref "SW2") (pin "B'") (pinfunction "S1_B'") (pintype "passive"))
      (node (ref "X2") (pin "3") (pinfunction "EN_3") (pintype "input"))
    )
    (net (code "60") (name "RTS") (class "Default")
      (node (ref "Q1") (pin "2") (pinfunction "E_2") (pintype "passive"))
      (node (ref "R6") (pin "1") (pinfunction "1_1") (pintype "passive"))
      (node (ref "U1") (pin "14") (pinfunction "~{RTS}_14") (pintype "output"))
    )
    (net (code "61") (name "RXD0") (class "Default")
      (node (ref "R9") (pin "1") (pinfunction "1_1") (pintype "passive"))
      (node (ref "X2") (pin "34") (pinfunction "RXD0_34") (pintype "input"))
    )
    (net (code "62") (name "SAO_IO1") (class "Default")
      (node (ref "J2") (pin "5") (pinfunction "5_5") (pintype "passive"))
      (node (ref "X2") (pin "27") (pinfunction "IO16_27") (pintype "bidirectional"))
    )
    (net (code "63") (name "SAO_IO2") (class "Default")
      (node (ref "J2") (pin "6") (pinfunction "6_6") (pintype "passive"))
      (node (ref "X2") (pin "28") (pinfunction "IO17_28") (pintype "bidirectional"))
    )
    (net (code "64") (name "SCL") (class "Default")
      (node (ref "J2") (pin "4") (pinfunction "4_4") (pintype "passive"))
      (node (ref "X2") (pin "36") (pinfunction "IO22_36") (pintype "bidirectional"))
    )
    (net (code "65") (name "SDA") (class "Default")
      (node (ref "J2") (pin "3") (pinfunction "3_3") (pintype "passive"))
      (node (ref "X2") (pin "37") (pinfunction "IO23_37") (pintype "bidirectional"))
    )
    (net (code "66") (name "TXD0") (class "Default")
      (node (ref "R11") (pin "1") (pinfunction "1_1") (pintype "passive"))
      (node (ref "X2") (pin "35") (pinfunction "TXD0_35") (pintype "output"))
    )
    (net (code "67") (name "VBAT") (class "Default")
      (node (ref "D2") (pin "A") (pinfunction "A_A") (pintype "passive"))
      (node (ref "R1") (pin "2") (pinfunction "2_2") (pintype "passive"))
      (node (ref "U27") (pin "1") (pinfunction "1_1") (pintype "passive"))
    )
    (net (code "68") (name "VBUS") (class "Default")
      (node (ref "D6") (pin "A") (pinfunction "A_A") (pintype "passive"))
      (node (ref "J3") (pin "A4/B9") (pinfunction "VBUS_A4/B9") (pintype "power_in"))
      (node (ref "J3") (pin "B4/A9") (pinfunction "VBUS_B4/A9") (pintype "power_in"))
      (node (ref "U4") (pin "4") (pinfunction "C3_4") (pintype "passive"))
    )
    (net (code "69") (name "VDD") (class "Default")
      (node (ref "C1") (pin "1") (pinfunction "1_1") (pintype "passive"))
      (node (ref "C10") (pin "1") (pinfunction "1_1") (pintype "passive"))
      (node (ref "C11") (pin "1") (pinfunction "1_1") (pintype "passive"))
      (node (ref "C12") (pin "1") (pinfunction "1_1") (pintype "passive"))
      (node (ref "C13") (pin "1") (pinfunction "1_1") (pintype "passive"))
      (node (ref "C14") (pin "1") (pinfunction "1_1") (pintype "passive"))
      (node (ref "C15") (pin "1") (pinfunction "1_1") (pintype "passive"))
      (node (ref "C16") (pin "1") (pinfunction "1_1") (pintype "passive"))
      (node (ref "C17") (pin "1") (pinfunction "1_1") (pintype "passive"))
      (node (ref "C19") (pin "1") (pinfunction "1_1") (pintype "passive"))
      (node (ref "C2") (pin "1") (pinfunction "1_1") (pintype "passive"))
      (node (ref "C20") (pin "1") (pinfunction "1_1") (pintype "passive"))
      (node (ref "C21") (pin "1") (pinfunction "1_1") (pintype "passive"))
      (node (ref "C22") (pin "1") (pinfunction "1_1") (pintype "passive"))
      (node (ref "C23") (pin "1") (pinfunction "1_1") (pintype "passive"))
      (node (ref "C24") (pin "1") (pinfunction "1_1") (pintype "passive"))
      (node (ref "C3") (pin "1") (pinfunction "1_1") (pintype "passive"))
      (node (ref "C4") (pin "1") (pinfunction "1_1") (pintype "passive"))
      (node (ref "C5") (pin "1") (pinfunction "1_1") (pintype "passive"))
      (node (ref "C6") (pin "1") (pinfunction "1_1") (pintype "passive"))
      (node (ref "C7") (pin "1") (pinfunction "1_1") (pintype "passive"))
      (node (ref "C8") (pin "1") (pinfunction "1_1") (pintype "passive"))
      (node (ref "D5") (pin "A") (pinfunction "A_A") (pintype "passive"))
      (node (ref "R7") (pin "2") (pinfunction "2_2") (pintype "passive"))
      (node (ref "U10") (pin "4") (pinfunction "VDD_4") (pintype "power_in"))
      (node (ref "U11") (pin "4") (pinfunction "VDD_4") (pintype "power_in"))
      (node (ref "U12") (pin "4") (pinfunction "VDD_4") (pintype "power_in"))
      (node (ref "U13") (pin "4") (pinfunction "VDD_4") (pintype "power_in"))
      (node (ref "U14") (pin "4") (pinfunction "VDD_4") (pintype "power_in"))
      (node (ref "U15") (pin "4") (pinfunction "VDD_4") (pintype "power_in"))
      (node (ref "U16") (pin "4") (pinfunction "VDD_4") (pintype "power_in"))
      (node (ref "U17") (pin "4") (pinfunction "VDD_4") (pintype "power_in"))
      (node (ref "U18") (pin "4") (pinfunction "VDD_4") (pintype "power_in"))
      (node (ref "U19") (pin "4") (pinfunction "VDD_4") (pintype "power_in"))
      (node (ref "U2") (pin "1") (pinfunction "IN_1") (pintype "power_in"))
      (node (ref "U20") (pin "4") (pinfunction "VDD_4") (pintype "power_in"))
      (node (ref "U21") (pin "4") (pinfunction "VDD_4") (pintype "power_in"))
      (node (ref "U22") (pin "4") (pinfunction "VDD_4") (pintype "power_in"))
      (node (ref "U23") (pin "4") (pinfunction "VDD_4") (pintype "power_in"))
      (node (ref "U24") (pin "4") (pinfunction "VDD_4") (pintype "power_in"))
      (node (ref "U25") (pin "4") (pinfunction "VDD_4") (pintype "power_in"))
      (node (ref "U26") (pin "4") (pinfunction "VDD_4") (pintype "power_in"))
      (node (ref "U5") (pin "1") (pinfunction "1_1") (pintype "passive"))
      (node (ref "U6") (pin "4") (pinfunction "VDD_4") (pintype "power_in"))
      (node (ref "U7") (pin "4") (pinfunction "VDD_4") (pintype "power_in"))
      (node (ref "U8") (pin "4") (pinfunction "VDD_4") (pintype "power_in"))
      (node (ref "U9") (pin "4") (pinfunction "VDD_4") (pintype "power_in"))
    )
    (net (code "70") (name "unconnected-(J3-SBU1-PadA8)") (class "Default")
      (node (ref "J3") (pin "A8") (pinfunction "SBU1_A8") (pintype "bidirectional"))
    )
    (net (code "71") (name "unconnected-(J3-SBU2-PadB8)") (class "Default")
      (node (ref "J3") (pin "B8") (pinfunction "SBU2_B8") (pintype "bidirectional"))
    )
    (net (code "72") (name "unconnected-(U1-NC.-Pad7)") (class "Default")
      (node (ref "U1") (pin "7") (pinfunction "NC._7") (pintype "no_connect"))
    )
    (net (code "73") (name "unconnected-(U1-R232-Pad15)") (class "Default")
      (node (ref "U1") (pin "15") (pinfunction "R232_15") (pintype "input"))
    )
    (net (code "74") (name "unconnected-(U1-~{CTS}-Pad9)") (class "Default")
      (node (ref "U1") (pin "9") (pinfunction "~{CTS}_9") (pintype "input"))
    )
    (net (code "75") (name "unconnected-(U1-~{DCD}-Pad12)") (class "Default")
      (node (ref "U1") (pin "12") (pinfunction "~{DCD}_12") (pintype "input"))
    )
    (net (code "76") (name "unconnected-(U1-~{DSR}-Pad10)") (class "Default")
      (node (ref "U1") (pin "10") (pinfunction "~{DSR}_10") (pintype "input"))
    )
    (net (code "77") (name "unconnected-(U1-~{OUT}-Pad8)") (class "Default")
      (node (ref "U1") (pin "8") (pinfunction "~{OUT}_8") (pintype "output"))
    )
    (net (code "78") (name "unconnected-(U1-~{RI}-Pad11)") (class "Default")
      (node (ref "U1") (pin "11") (pinfunction "~{RI}_11") (pintype "input"))
    )
    (net (code "79") (name "unconnected-(U2-P4-Pad4)") (class "Default")
      (node (ref "U2") (pin "4") (pinfunction "P4_4") (pintype "bidirectional"))
    )
    (net (code "80") (name "unconnected-(U4-C1-Pad1)") (class "Default")
      (node (ref "U4") (pin "1") (pinfunction "C1_1") (pintype "passive"))
    )
    (net (code "81") (name "unconnected-(U4-C2-Pad3)") (class "Default")
      (node (ref "U4") (pin "3") (pinfunction "C2_3") (pintype "passive"))
    )
    (net (code "82") (name "unconnected-(U5-Pad3)") (class "Default")
      (node (ref "U5") (pin "3") (pinfunction "3_3") (pintype "passive"))
    )
    (net (code "83") (name "unconnected-(U26-DO-Pad1)") (class "Default")
      (node (ref "U26") (pin "1") (pinfunction "DO_1") (pintype "output"))
    )
    (net (code "84") (name "unconnected-(X2-CLK-Pad20)") (class "Default")
      (node (ref "X2") (pin "20") (pinfunction "CLK_20") (pintype "bidirectional"))
    )
    (net (code "85") (name "unconnected-(X2-CMD-Pad19)") (class "Default")
      (node (ref "X2") (pin "19") (pinfunction "CMD_19") (pintype "bidirectional"))
    )
    (net (code "86") (name "unconnected-(X2-SD0-Pad21)") (class "Default")
      (node (ref "X2") (pin "21") (pinfunction "SD0_21") (pintype "bidirectional"))
    )
    (net (code "87") (name "unconnected-(X2-SD1-Pad22)") (class "Default")
      (node (ref "X2") (pin "22") (pinfunction "SD1_22") (pintype "bidirectional"))
    )
    (net (code "88") (name "unconnected-(X2-SD2-Pad17)") (class "Default")
      (node (ref "X2") (pin "17") (pinfunction "SD2_17") (pintype "bidirectional"))
    )
    (net (code "89") (name "unconnected-(X2-SD3-Pad18)") (class "Default")
      (node (ref "X2") (pin "18") (pinfunction "SD3_18") (pintype "bidirectional"))
    )
  )
)
